# Power_12v.net
KiCad netlist of a schematic drawn in Altium Designer
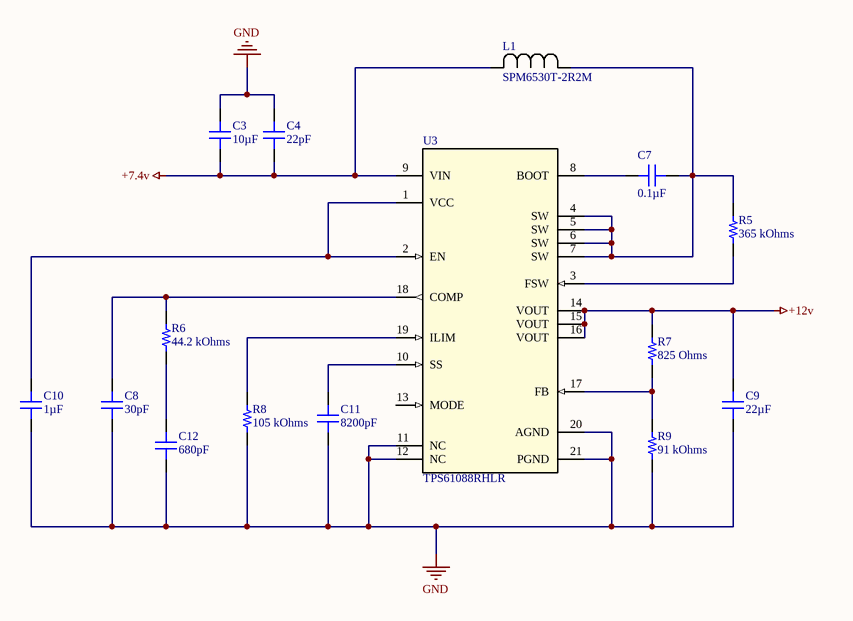
[diagram p0: Power_12v.SchDoc]

(export (version "E")
  (design (tool "Eeschema 10.0.6"))
  (components
    (comp (ref "C3")
      (value "10µF")
      (footprint "CAP 1210_3225 - 2.8MM")
      (description "CAP CER 10UF 50V X7S 1210")
      (fields
        (field (name "PART NUMBER") "GCJ32EC71H106KA01L")
        (field (name "MANUFACTURER") "Murata Electronics")
      )
      (libsource (lib "Celestial Altium Library - altium_library") (part "Capacitor"))
    )
    (comp (ref "C4")
      (value "22pF")
      (footprint "CAP 0603_1608")
      (description "CAP CER 22PF 25V C0G/NP0 0603")
      (fields (field (name "PART NUMBER") "06033A220KAT2A") (field (name "MANUFACTURER") "AVX Corporation"))
      (libsource (lib "Celestial Altium Library - altium_library") (part "Capacitor"))
    )
    (comp (ref "C7")
      (value "0.1µF")
      (footprint "CAP 0603_1608")
      (description "CAP CER 0.1UF 16V X7R 0603")
      (fields (field (name "PART NUMBER") "0603YC104JAT4A") (field (name "MANUFACTURER") "AVX Corporation"))
      (libsource (lib "Celestial Altium Library - altium_library") (part "Capacitor"))
    )
    (comp (ref "C8")
      (value "30pF")
      (footprint "CAP 0603_1608")
      (description "CAP CER 30PF 50V C0G/NP0 0805")
      (fields (field (name "PART NUMBER") "C0805C300J5GACTU") (field (name "MANUFACTURER") "KEMET"))
      (libsource (lib "Celestial Altium Library - altium_library") (part "Capacitor"))
    )
    (comp (ref "C9")
      (value "22µF")
      (footprint "CAP 1210_3225 - 2.8MM")
      (description "CAP CER 22UF 25V X7R 1210")
      (fields
        (field (name "PART NUMBER") "GRM32ER71E226ME15K")
        (field (name "MANUFACTURER") "Murata Electronics")
      )
      (libsource (lib "Celestial Altium Library - altium_library") (part "Capacitor"))
    )
    (comp (ref "C10")
      (value "1µF")
      (footprint "CAP 0603_1608")
      (description "CAP CER 1UF 16V X5R 0603")
      (fields (field (name "PART NUMBER") "C0603C105K4PACTU") (field (name "MANUFACTURER") "KEMET"))
      (libsource (lib "Celestial Altium Library - altium_library") (part "Capacitor"))
    )
    (comp (ref "C11")
      (value "8200pF")
      (footprint "CAP 0603_1608")
      (description "CAP CER 8200PF 50V BX 0805")
      (fields (field (name "PART NUMBER") "CDR31BX822AKUS7185") (field (name "MANUFACTURER") "KEMET"))
      (libsource (lib "Celestial Altium Library - altium_library") (part "Capacitor"))
    )
    (comp (ref "C12")
      (value "680pF")
      (footprint "CAP 0603_1608")
      (description "CAP CER 680PF 50V C0G/NPO 0805")
      (fields (field (name "PART NUMBER") "CC0805JRNPO9BN681") (field (name "MANUFACTURER") "Yageo"))
      (libsource (lib "Celestial Altium Library - altium_library") (part "Capacitor"))
    )
    (comp (ref "L1")
      (value "SPM6530T-2R2M")
      (footprint "IND_SPM6530_TDK")
      (description "No Description Available")
      (fields (field (name "COPYRIGHT") "Copyright (C) 2018 Accelerated Designs. All rights reserved"))
      (libsource (lib "SPM6530T-2R2M") (part "SPM6530T-2R2M"))
    )
    (comp (ref "R5")
      (value "365 kOhms")
      (footprint "RES 0603_1608")
      (description "RES SMD 365K OHM 1% 1/8W 0805")
      (fields (field (name "PART NUMBER") "RC0805FR-07365KL") (field (name "MANUFACTURER") "Yageo"))
      (libsource (lib "Celestial Altium Library - altium_library") (part "Resistor"))
    )
    (comp (ref "R6")
      (value "44.2 kOhms")
      (footprint "RES 0603_1608")
      (description "RES SMD 44.2K OHM 1% 1/8W 0805")
      (fields (field (name "PART NUMBER") "KTR10EZPF4422") (field (name "MANUFACTURER") "Rohm Semiconductor"))
      (libsource (lib "Celestial Altium Library - altium_library") (part "Resistor"))
    )
    (comp (ref "R7")
      (value "825 Ohms")
      (footprint "RES 0603_1608")
      (description "RES 825 OHM 1% 1/8W 0805")
      (fields
        (field (name "PART NUMBER") "RMCF0805FT825R")
        (field (name "MANUFACTURER") "Stackpole Electronics Inc")
      )
      (libsource (lib "Celestial Altium Library - altium_library") (part "Resistor"))
    )
    (comp (ref "R8")
      (value "105 kOhms")
      (footprint "RES 0603_1608")
      (description "RES SMD 105K OHM 1% 1/10W 0603")
      (fields (field (name "PART NUMBER") "RC0603FR-07105KL") (field (name "MANUFACTURER") "Yageo"))
      (libsource (lib "Celestial Altium Library - altium_library") (part "Resistor"))
    )
    (comp (ref "R9")
      (value "91 kOhms")
      (footprint "RES 0805_2012")
      (description "RES SMD 91K OHM 5% 1/8W 0805")
      (fields (field (name "PART NUMBER") "CRCW080591K0JNEA") (field (name "MANUFACTURER") "Vishay Dale"))
      (libsource (lib "") (part "Resistor_1"))
    )
    (comp (ref "U3")
      (value "TPS61088RHLR")
      (footprint "RHL0020A")
      (description "No Description Available")
      (fields
        (field (name "ALTERNATE_PARTNUMBER") "TPS61088RHLT")
        (field (name "MANUFACTURER") "Texas Instruments")
        (field (name "COPYRIGHT") "Copyright (C) 2018 Accelerated Designs. All rights reserved")
      )
      (libsource (lib "TPS61088RHLR") (part "TPS61088RHLR"))
    )
  )
  (nets
    (net (code "1") (name "+7.4v") (class "Default")
      (node (ref "C3") (pin "1") (pinfunction "1_1") (pintype "passive"))
      (node (ref "C4") (pin "1") (pinfunction "1_1") (pintype "passive"))
      (node (ref "L1") (pin "2") (pinfunction "2_2") (pintype "passive"))
      (node (ref "U3") (pin "9") (pinfunction "VIN_9") (pintype "power_in"))
    )
    (net (code "2") (name "+12v") (class "Default")
      (node (ref "C9") (pin "2") (pinfunction "2_2") (pintype "passive"))
      (node (ref "R7") (pin "2") (pinfunction "2_2") (pintype "passive"))
      (node (ref "U3") (pin "14") (pinfunction "VOUT_14") (pintype "power_in"))
      (node (ref "U3") (pin "15") (pinfunction "VOUT_15") (pintype "power_in"))
      (node (ref "U3") (pin "16") (pinfunction "VOUT_16") (pintype "power_in"))
    )
    (net (code "3") (name "GND") (class "Default")
      (node (ref "C10") (pin "1") (pinfunction "1_1") (pintype "passive"))
      (node (ref "C11") (pin "1") (pinfunction "1_1") (pintype "passive"))
      (node (ref "C12") (pin "1") (pinfunction "1_1") (pintype "passive"))
      (node (ref "C3") (pin "2") (pinfunction "2_2") (pintype "passive"))
      (node (ref "C4") (pin "2") (pinfunction "2_2") (pintype "passive"))
      (node (ref "C8") (pin "1") (pinfunction "1_1") (pintype "passive"))
      (node (ref "C9") (pin "1") (pinfunction "1_1") (pintype "passive"))
      (node (ref "R8") (pin "1") (pinfunction "1_1") (pintype "passive"))
      (node (ref "R9") (pin "2") (pinfunction "2_2") (pintype "passive"))
      (node (ref "U3") (pin "11") (pinfunction "NC_11") (pintype "passive"))
      (node (ref "U3") (pin "12") (pinfunction "NC_12") (pintype "passive"))
      (node (ref "U3") (pin "20") (pinfunction "AGND_20") (pintype "power_in"))
      (node (ref "U3") (pin "21") (pinfunction "PGND_21") (pintype "power_in"))
    )
    (net (code "4") (name "Net-(C7-Pad2)") (class "Default")
      (node (ref "C7") (pin "2") (pinfunction "2_2") (pintype "passive"))
      (node (ref "L1") (pin "1") (pinfunction "1_1") (pintype "passive"))
      (node (ref "R5") (pin "2") (pinfunction "2_2") (pintype "passive"))
      (node (ref "U3") (pin "4") (pinfunction "SW_4") (pintype "power_in"))
      (node (ref "U3") (pin "5") (pinfunction "SW_5") (pintype "power_in"))
      (node (ref "U3") (pin "6") (pinfunction "SW_6") (pintype "power_in"))
      (node (ref "U3") (pin "7") (pinfunction "SW_7") (pintype "power_in"))
    )
    (net (code "5") (name "Net-(C12-Pad2)") (class "Default")
      (node (ref "C12") (pin "2") (pinfunction "2_2") (pintype "passive"))
      (node (ref "R6") (pin "1") (pinfunction "1_1") (pintype "passive"))
    )
    (net (code "6") (name "Net-(U3-BOOT)") (class "Default")
      (node (ref "C7") (pin "1") (pinfunction "1_1") (pintype "passive"))
      (node (ref "U3") (pin "8") (pinfunction "BOOT_8") (pintype "power_in"))
    )
    (net (code "7") (name "Net-(U3-COMP)") (class "Default")
      (node (ref "C8") (pin "2") (pinfunction "2_2") (pintype "passive"))
      (node (ref "R6") (pin "2") (pinfunction "2_2") (pintype "passive"))
      (node (ref "U3") (pin "18") (pinfunction "COMP_18") (pintype "output"))
    )
    (net (code "8") (name "Net-(U3-EN)") (class "Default")
      (node (ref "C10") (pin "2") (pinfunction "2_2") (pintype "passive"))
      (node (ref "U3") (pin "1") (pinfunction "VCC_1") (pintype "power_in"))
      (node (ref "U3") (pin "2") (pinfunction "EN_2") (pintype "input"))
    )
    (net (code "9") (name "Net-(U3-FB)") (class "Default")
      (node (ref "R7") (pin "1") (pinfunction "1_1") (pintype "passive"))
      (node (ref "R9") (pin "1") (pinfunction "1_1") (pintype "passive"))
      (node (ref "U3") (pin "17") (pinfunction "FB_17") (pintype "input"))
    )
    (net (code "10") (name "Net-(U3-FSW)") (class "Default")
      (node (ref "R5") (pin "1") (pinfunction "1_1") (pintype "passive"))
      (node (ref "U3") (pin "3") (pinfunction "FSW_3") (pintype "input"))
    )
    (net (code "11") (name "Net-(U3-ILIM)") (class "Default")
      (node (ref "R8") (pin "2") (pinfunction "2_2") (pintype "passive"))
      (node (ref "U3") (pin "19") (pinfunction "ILIM_19") (pintype "input"))
    )
    (net (code "12") (name "Net-(U3-SS)") (class "Default")
      (node (ref "C11") (pin "2") (pinfunction "2_2") (pintype "passive"))
      (node (ref "U3") (pin "10") (pinfunction "SS_10") (pintype "input"))
    )
    (net (code "13") (name "unconnected-(U3-MODE-Pad13)") (class "Default")
      (node (ref "U3") (pin "13") (pinfunction "MODE_13") (pintype "input"))
    )
  )
)
